# Power_Supply.net
KiCad netlist of a schematic drawn in Altium Designer
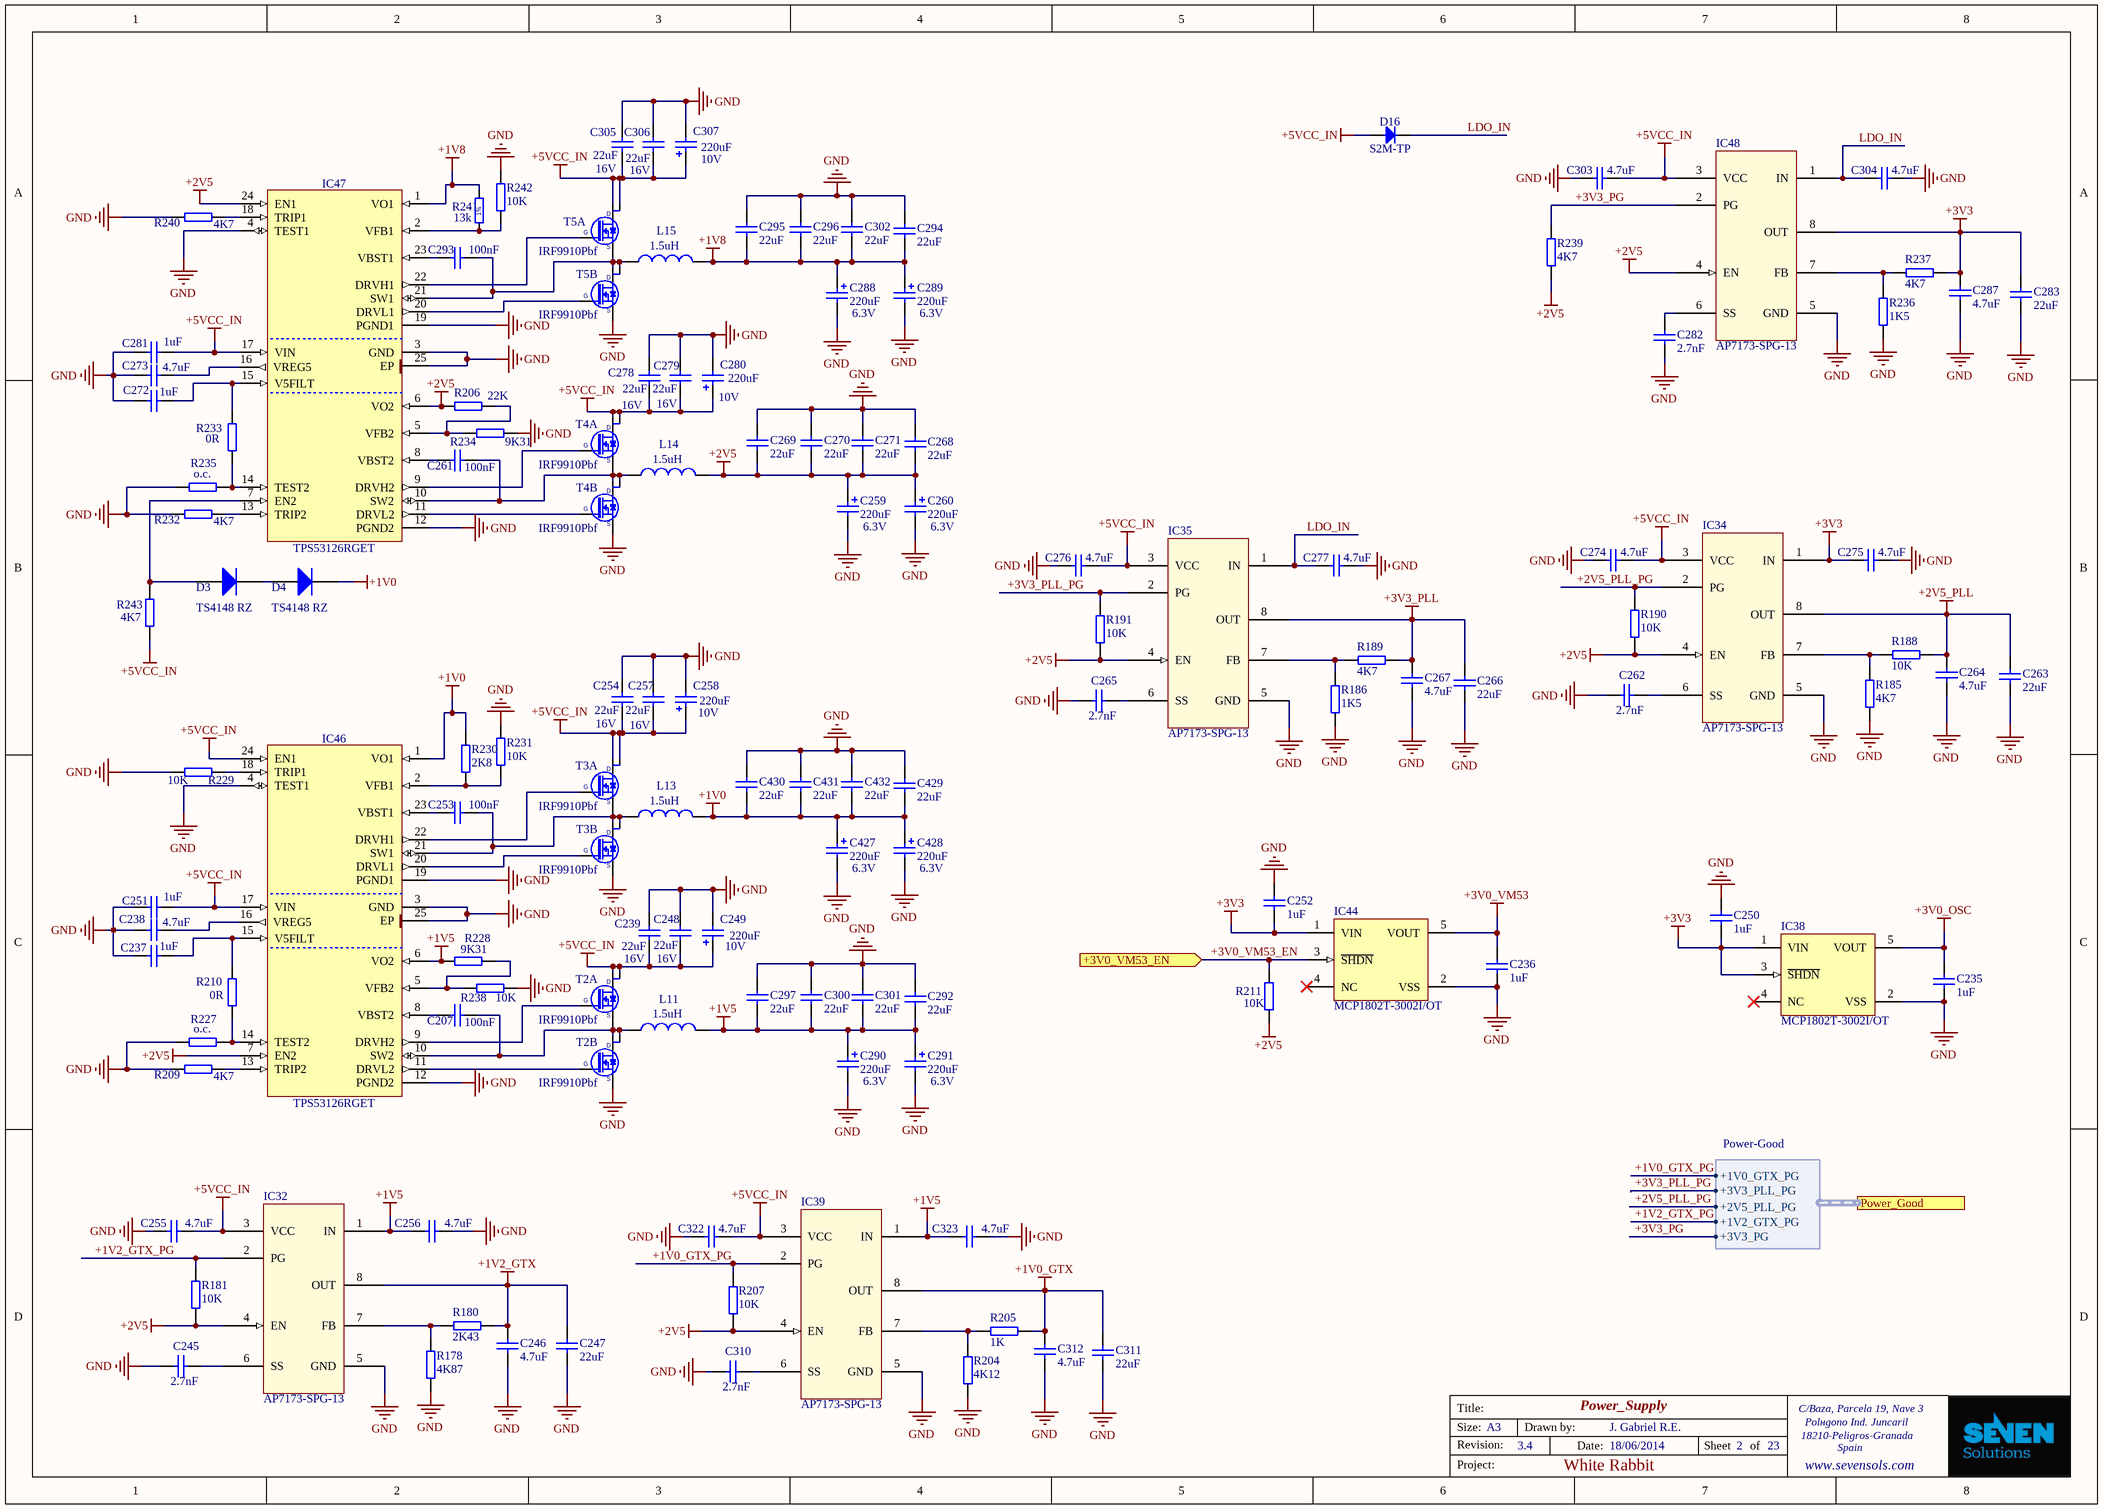
[diagram p0: Power_Supply.SchDoc]

(export (version "E")
  (design (tool "Eeschema 10.0.6"))
  (components
    (comp (ref "C207")
      (value "100nF")
      (footprint "CC1005-0402")
      (description "Capacitor")
      (fields
        (field (name "TOLERANCE") "±10%")
        (field (name "VOLTAGE") "16V")
        (field (name "PUBLISHER") "Altium Limited")
      )
      (libsource (lib "wr_switch") (part "Cap"))
    )
    (comp (ref "C235")
      (value "1uF")
      (footprint "CC1005-0402")
      (description "Capacitor")
      (fields
        (field (name "TOLERANCE") "±10%")
        (field (name "VOLTAGE") "16V")
        (field (name "PUBLISHER") "Altium Limited")
      )
      (libsource (lib "wr_switch") (part "Cap"))
    )
    (comp (ref "C236")
      (value "1uF")
      (footprint "CC1005-0402")
      (description "Capacitor")
      (fields
        (field (name "TOLERANCE") "±10%")
        (field (name "VOLTAGE") "16V")
        (field (name "PUBLISHER") "Altium Limited")
      )
      (libsource (lib "wr_switch") (part "Cap"))
    )
    (comp (ref "C237")
      (value "1uF")
      (footprint "CC1005-0402")
      (description "Capacitor")
      (fields
        (field (name "TOLERANCE") "±10%")
        (field (name "VOLTAGE") "16V")
        (field (name "PUBLISHER") "Altium Limited")
      )
      (libsource (lib "wr_switch") (part "Cap"))
    )
    (comp (ref "C238")
      (value "4.7uF")
      (footprint "CC1608-0603")
      (description "Capacitor")
      (fields
        (field (name "TOLERANCE") "±10%")
        (field (name "VOLTAGE") "10V")
        (field (name "PUBLISHER") "Altium Limited")
      )
      (libsource (lib "wr_switch") (part "Cap"))
    )
    (comp (ref "C239")
      (value "22uF")
      (footprint "CC2012-0805")
      (description "Capacitor")
      (fields
        (field (name "TOLERANCE") "±10%")
        (field (name "VOLTAGE") "16V")
        (field (name "Comment") "22uF 16V")
        (field (name "PUBLISHER") "Altium Limited")
      )
      (libsource (lib "wr_switch") (part "Cap"))
    )
    (comp (ref "C245")
      (value "2.7nF")
      (footprint "CC1005-0402")
      (description "Capacitor")
      (fields
        (field (name "TOLERANCE") "±10%")
        (field (name "VOLTAGE") "50V")
        (field (name "PUBLISHER") "Altium Limited")
      )
      (libsource (lib "wr_switch") (part "Cap"))
    )
    (comp (ref "C246")
      (value "4.7uF")
      (footprint "CC1608-0603")
      (description "Capacitor")
      (fields
        (field (name "TOLERANCE") "±10%")
        (field (name "VOLTAGE") "10V")
        (field (name "PUBLISHER") "Altium Limited")
      )
      (libsource (lib "wr_switch") (part "Cap"))
    )
    (comp (ref "C247")
      (value "22uF")
      (footprint "CC2012-0805")
      (description "Capacitor")
      (fields
        (field (name "TOLERANCE") "±20%")
        (field (name "VOLTAGE") "6.3V")
        (field (name "PUBLISHER") "Altium Limited")
      )
      (libsource (lib "wr_switch") (part "Cap"))
    )
    (comp (ref "C248")
      (value "22uF")
      (footprint "CC2012-0805")
      (description "Capacitor")
      (fields
        (field (name "TOLERANCE") "±10%")
        (field (name "VOLTAGE") "16V")
        (field (name "Comment") "22uF 16V")
        (field (name "PUBLISHER") "Altium Limited")
      )
      (libsource (lib "wr_switch") (part "Cap"))
    )
    (comp (ref "C249")
      (value "220uF")
      (footprint "D")
      (description "Polarized Capacitor Tantalum")
      (fields
        (field (name "TOLERANCE") "±20%")
        (field (name "VOLTAGE") "10V")
        (field (name "Comment") "220uF 10V")
        (field (name "PUBLISHER") "Altium Limited")
      )
      (libsource (lib "wr_switch") (part "Cap Pol1"))
    )
    (comp (ref "C250")
      (value "1uF")
      (footprint "CC1005-0402")
      (description "Capacitor")
      (fields
        (field (name "TOLERANCE") "±10%")
        (field (name "VOLTAGE") "16V")
        (field (name "PUBLISHER") "Altium Limited")
      )
      (libsource (lib "wr_switch") (part "Cap"))
    )
    (comp (ref "C251")
      (value "1uF")
      (footprint "CC1005-0402")
      (description "Capacitor")
      (fields
        (field (name "TOLERANCE") "±10%")
        (field (name "VOLTAGE") "16V")
        (field (name "PUBLISHER") "Altium Limited")
      )
      (libsource (lib "wr_switch") (part "Cap"))
    )
    (comp (ref "C252")
      (value "1uF")
      (footprint "CC1005-0402")
      (description "Capacitor")
      (fields
        (field (name "TOLERANCE") "±10%")
        (field (name "VOLTAGE") "16V")
        (field (name "PUBLISHER") "Altium Limited")
      )
      (libsource (lib "wr_switch") (part "Cap"))
    )
    (comp (ref "C253")
      (value "100nF")
      (footprint "CC1005-0402")
      (description "Capacitor")
      (fields
        (field (name "TOLERANCE") "±10%")
        (field (name "VOLTAGE") "16V")
        (field (name "PUBLISHER") "Altium Limited")
      )
      (libsource (lib "wr_switch") (part "Cap"))
    )
    (comp (ref "C254")
      (value "22uF")
      (footprint "CC2012-0805")
      (description "Capacitor")
      (fields
        (field (name "TOLERANCE") "±10%")
        (field (name "VOLTAGE") "16V")
        (field (name "Comment") "22uF 16V")
        (field (name "PUBLISHER") "Altium Limited")
      )
      (libsource (lib "wr_switch") (part "Cap"))
    )
    (comp (ref "C255")
      (value "4.7uF")
      (footprint "CC1608-0603")
      (description "Capacitor")
      (fields
        (field (name "TOLERANCE") "±10%")
        (field (name "VOLTAGE") "10V")
        (field (name "PUBLISHER") "Altium Limited")
      )
      (libsource (lib "wr_switch") (part "Cap"))
    )
    (comp (ref "C256")
      (value "4.7uF")
      (footprint "CC1608-0603")
      (description "Capacitor")
      (fields
        (field (name "TOLERANCE") "±10%")
        (field (name "VOLTAGE") "10V")
        (field (name "PUBLISHER") "Altium Limited")
      )
      (libsource (lib "wr_switch") (part "Cap"))
    )
    (comp (ref "C257")
      (value "22uF")
      (footprint "CC2012-0805")
      (description "Capacitor")
      (fields
        (field (name "TOLERANCE") "±10%")
        (field (name "VOLTAGE") "16V")
        (field (name "Comment") "22uF 16V")
        (field (name "PUBLISHER") "Altium Limited")
      )
      (libsource (lib "wr_switch") (part "Cap"))
    )
    (comp (ref "C258")
      (value "220uF")
      (footprint "D")
      (description "Polarized Capacitor Tantalum")
      (fields
        (field (name "TOLERANCE") "±20%")
        (field (name "VOLTAGE") "10V")
        (field (name "Comment") "220uF 10V")
        (field (name "PUBLISHER") "Altium Limited")
      )
      (libsource (lib "wr_switch") (part "Cap Pol1"))
    )
    (comp (ref "C259")
      (value "220uF")
      (footprint "D")
      (description "Polarized Capacitor Tantalum")
      (fields
        (field (name "TOLERANCE") "±20%")
        (field (name "VOLTAGE") "6.3V")
        (field (name "PUBLISHER") "Altium Limited")
      )
      (libsource (lib "wr_switch") (part "Cap Pol1"))
    )
    (comp (ref "C260")
      (value "220uF")
      (footprint "D")
      (description "Polarized Capacitor Tantalum")
      (fields
        (field (name "TOLERANCE") "±20%")
        (field (name "VOLTAGE") "6.3V")
        (field (name "PUBLISHER") "Altium Limited")
      )
      (libsource (lib "wr_switch") (part "Cap Pol1"))
    )
    (comp (ref "C261")
      (value "100nF")
      (footprint "CC1005-0402")
      (description "Capacitor")
      (fields
        (field (name "TOLERANCE") "±10%")
        (field (name "VOLTAGE") "16V")
        (field (name "PUBLISHER") "Altium Limited")
      )
      (libsource (lib "wr_switch") (part "Cap"))
    )
    (comp (ref "C262")
      (value "2.7nF")
      (footprint "CC1005-0402")
      (description "Capacitor")
      (fields
        (field (name "TOLERANCE") "±10%")
        (field (name "VOLTAGE") "50V")
        (field (name "PUBLISHER") "Altium Limited")
      )
      (libsource (lib "wr_switch") (part "Cap"))
    )
    (comp (ref "C263")
      (value "22uF")
      (footprint "CC2012-0805")
      (description "Capacitor")
      (fields
        (field (name "TOLERANCE") "±20%")
        (field (name "VOLTAGE") "6.3V")
        (field (name "PUBLISHER") "Altium Limited")
      )
      (libsource (lib "wr_switch") (part "Cap"))
    )
    (comp (ref "C264")
      (value "4.7uF")
      (footprint "CC1608-0603")
      (description "Capacitor")
      (fields
        (field (name "TOLERANCE") "±10%")
        (field (name "VOLTAGE") "10V")
        (field (name "PUBLISHER") "Altium Limited")
      )
      (libsource (lib "wr_switch") (part "Cap"))
    )
    (comp (ref "C265")
      (value "2.7nF")
      (footprint "CC1005-0402")
      (description "Capacitor")
      (fields
        (field (name "TOLERANCE") "±10%")
        (field (name "VOLTAGE") "50V")
        (field (name "PUBLISHER") "Altium Limited")
      )
      (libsource (lib "wr_switch") (part "Cap"))
    )
    (comp (ref "C266")
      (value "22uF")
      (footprint "CC2012-0805")
      (description "Capacitor")
      (fields
        (field (name "TOLERANCE") "±20%")
        (field (name "VOLTAGE") "6.3V")
        (field (name "PUBLISHER") "Altium Limited")
      )
      (libsource (lib "wr_switch") (part "Cap"))
    )
    (comp (ref "C267")
      (value "4.7uF")
      (footprint "CC1608-0603")
      (description "Capacitor")
      (fields
        (field (name "TOLERANCE") "±10%")
        (field (name "VOLTAGE") "10V")
        (field (name "PUBLISHER") "Altium Limited")
      )
      (libsource (lib "wr_switch") (part "Cap"))
    )
    (comp (ref "C268")
      (value "22uF")
      (footprint "CC2012-0805")
      (description "Capacitor")
      (fields
        (field (name "TOLERANCE") "±20%")
        (field (name "VOLTAGE") "6.3V")
        (field (name "PUBLISHER") "Altium Limited")
      )
      (libsource (lib "wr_switch") (part "Cap"))
    )
    (comp (ref "C269")
      (value "22uF")
      (footprint "CC2012-0805")
      (description "Capacitor")
      (fields
        (field (name "TOLERANCE") "±20%")
        (field (name "VOLTAGE") "6.3V")
        (field (name "PUBLISHER") "Altium Limited")
      )
      (libsource (lib "wr_switch") (part "Cap"))
    )
    (comp (ref "C270")
      (value "22uF")
      (footprint "CC2012-0805")
      (description "Capacitor")
      (fields
        (field (name "TOLERANCE") "±20%")
        (field (name "VOLTAGE") "6.3V")
        (field (name "PUBLISHER") "Altium Limited")
      )
      (libsource (lib "wr_switch") (part "Cap"))
    )
    (comp (ref "C271")
      (value "22uF")
      (footprint "CC2012-0805")
      (description "Capacitor")
      (fields
        (field (name "TOLERANCE") "±20%")
        (field (name "VOLTAGE") "6.3V")
        (field (name "PUBLISHER") "Altium Limited")
      )
      (libsource (lib "wr_switch") (part "Cap"))
    )
    (comp (ref "C272")
      (value "1uF")
      (footprint "CC1005-0402")
      (description "Capacitor")
      (fields
        (field (name "TOLERANCE") "±10%")
        (field (name "VOLTAGE") "16V")
        (field (name "PUBLISHER") "Altium Limited")
      )
      (libsource (lib "wr_switch") (part "Cap"))
    )
    (comp (ref "C273")
      (value "4.7uF")
      (footprint "CC1608-0603")
      (description "Capacitor")
      (fields
        (field (name "TOLERANCE") "±10%")
        (field (name "VOLTAGE") "10V")
        (field (name "PUBLISHER") "Altium Limited")
      )
      (libsource (lib "wr_switch") (part "Cap"))
    )
    (comp (ref "C274")
      (value "4.7uF")
      (footprint "CC1608-0603")
      (description "Capacitor")
      (fields
        (field (name "TOLERANCE") "±10%")
        (field (name "VOLTAGE") "10V")
        (field (name "PUBLISHER") "Altium Limited")
      )
      (libsource (lib "wr_switch") (part "Cap"))
    )
    (comp (ref "C275")
      (value "4.7uF")
      (footprint "CC1608-0603")
      (description "Capacitor")
      (fields
        (field (name "TOLERANCE") "±10%")
        (field (name "VOLTAGE") "10V")
        (field (name "PUBLISHER") "Altium Limited")
      )
      (libsource (lib "wr_switch") (part "Cap"))
    )
    (comp (ref "C276")
      (value "4.7uF")
      (footprint "CC1608-0603")
      (description "Capacitor")
      (fields
        (field (name "TOLERANCE") "±10%")
        (field (name "VOLTAGE") "10V")
        (field (name "PUBLISHER") "Altium Limited")
      )
      (libsource (lib "wr_switch") (part "Cap"))
    )
    (comp (ref "C277")
      (value "4.7uF")
      (footprint "CC1608-0603")
      (description "Capacitor")
      (fields
        (field (name "TOLERANCE") "±10%")
        (field (name "VOLTAGE") "10V")
        (field (name "PUBLISHER") "Altium Limited")
      )
      (libsource (lib "wr_switch") (part "Cap"))
    )
    (comp (ref "C278")
      (value "22uF")
      (footprint "CC2012-0805")
      (description "Capacitor")
      (fields
        (field (name "TOLERANCE") "±10%")
        (field (name "VOLTAGE") "16V")
        (field (name "Comment") "22uF 16V")
        (field (name "PUBLISHER") "Altium Limited")
      )
      (libsource (lib "wr_switch") (part "Cap"))
    )
    (comp (ref "C279")
      (value "22uF")
      (footprint "CC2012-0805")
      (description "Capacitor")
      (fields
        (field (name "TOLERANCE") "±10%")
        (field (name "VOLTAGE") "16V")
        (field (name "Comment") "22uF 16V")
        (field (name "PUBLISHER") "Altium Limited")
      )
      (libsource (lib "wr_switch") (part "Cap"))
    )
    (comp (ref "C280")
      (value "220uF")
      (footprint "D")
      (description "Polarized Capacitor Tantalum")
      (fields
        (field (name "TOLERANCE") "±20%")
        (field (name "VOLTAGE") "10V")
        (field (name "Comment") "220uF 10V")
        (field (name "PUBLISHER") "Altium Limited")
      )
      (libsource (lib "wr_switch") (part "Cap Pol1"))
    )
    (comp (ref "C281")
      (value "1uF")
      (footprint "CC1005-0402")
      (description "Capacitor")
      (fields
        (field (name "TOLERANCE") "±10%")
        (field (name "VOLTAGE") "16V")
        (field (name "PUBLISHER") "Altium Limited")
      )
      (libsource (lib "wr_switch") (part "Cap"))
    )
    (comp (ref "C282")
      (value "2.7nF")
      (footprint "CC1005-0402")
      (description "Capacitor")
      (fields
        (field (name "TOLERANCE") "±10%")
        (field (name "VOLTAGE") "50V")
        (field (name "PUBLISHER") "Altium Limited")
      )
      (libsource (lib "wr_switch") (part "Cap"))
    )
    (comp (ref "C283")
      (value "22uF")
      (footprint "CC2012-0805")
      (description "Capacitor")
      (fields
        (field (name "TOLERANCE") "±20%")
        (field (name "VOLTAGE") "6.3V")
        (field (name "PUBLISHER") "Altium Limited")
      )
      (libsource (lib "wr_switch") (part "Cap"))
    )
    (comp (ref "C287")
      (value "4.7uF")
      (footprint "CC1608-0603")
      (description "Capacitor")
      (fields
        (field (name "TOLERANCE") "±10%")
        (field (name "VOLTAGE") "10V")
        (field (name "PUBLISHER") "Altium Limited")
      )
      (libsource (lib "wr_switch") (part "Cap"))
    )
    (comp (ref "C288")
      (value "220uF")
      (footprint "D")
      (description "Polarized Capacitor Tantalum")
      (fields
        (field (name "TOLERANCE") "±20%")
        (field (name "VOLTAGE") "6.3V")
        (field (name "PUBLISHER") "Altium Limited")
      )
      (libsource (lib "wr_switch") (part "Cap Pol1"))
    )
    (comp (ref "C289")
      (value "220uF")
      (footprint "D")
      (description "Polarized Capacitor Tantalum")
      (fields
        (field (name "TOLERANCE") "±20%")
        (field (name "VOLTAGE") "6.3V")
        (field (name "PUBLISHER") "Altium Limited")
      )
      (libsource (lib "wr_switch") (part "Cap Pol1"))
    )
    (comp (ref "C290")
      (value "220uF")
      (footprint "D")
      (description "Polarized Capacitor Tantalum")
      (fields
        (field (name "TOLERANCE") "±20%")
        (field (name "VOLTAGE") "6.3V")
        (field (name "PUBLISHER") "Altium Limited")
      )
      (libsource (lib "wr_switch") (part "Cap Pol1"))
    )
    (comp (ref "C291")
      (value "220uF")
      (footprint "D")
      (description "Polarized Capacitor Tantalum")
      (fields
        (field (name "TOLERANCE") "±20%")
        (field (name "VOLTAGE") "6.3V")
        (field (name "PUBLISHER") "Altium Limited")
      )
      (libsource (lib "wr_switch") (part "Cap Pol1"))
    )
    (comp (ref "C292")
      (value "22uF")
      (footprint "CC2012-0805")
      (description "Capacitor")
      (fields
        (field (name "TOLERANCE") "±20%")
        (field (name "VOLTAGE") "6.3V")
        (field (name "PUBLISHER") "Altium Limited")
      )
      (libsource (lib "wr_switch") (part "Cap"))
    )
    (comp (ref "C293")
      (value "100nF")
      (footprint "CC1005-0402")
      (description "Capacitor")
      (fields
        (field (name "TOLERANCE") "±10%")
        (field (name "VOLTAGE") "16V")
        (field (name "PUBLISHER") "Altium Limited")
      )
      (libsource (lib "wr_switch") (part "Cap"))
    )
    (comp (ref "C294")
      (value "22uF")
      (footprint "CC2012-0805")
      (description "Capacitor")
      (fields
        (field (name "TOLERANCE") "±20%")
        (field (name "VOLTAGE") "6.3V")
        (field (name "PUBLISHER") "Altium Limited")
      )
      (libsource (lib "wr_switch") (part "Cap"))
    )
    (comp (ref "C295")
      (value "22uF")
      (footprint "CC2012-0805")
      (description "Capacitor")
      (fields
        (field (name "TOLERANCE") "±20%")
        (field (name "VOLTAGE") "6.3V")
        (field (name "PUBLISHER") "Altium Limited")
      )
      (libsource (lib "wr_switch") (part "Cap"))
    )
    (comp (ref "C296")
      (value "22uF")
      (footprint "CC2012-0805")
      (description "Capacitor")
      (fields
        (field (name "TOLERANCE") "±20%")
        (field (name "VOLTAGE") "6.3V")
        (field (name "PUBLISHER") "Altium Limited")
      )
      (libsource (lib "wr_switch") (part "Cap"))
    )
    (comp (ref "C297")
      (value "22uF")
      (footprint "CC2012-0805")
      (description "Capacitor")
      (fields
        (field (name "TOLERANCE") "±20%")
        (field (name "VOLTAGE") "6.3V")
        (field (name "PUBLISHER") "Altium Limited")
      )
      (libsource (lib "wr_switch") (part "Cap"))
    )
    (comp (ref "C300")
      (value "22uF")
      (footprint "CC2012-0805")
      (description "Capacitor")
      (fields
        (field (name "TOLERANCE") "±20%")
        (field (name "VOLTAGE") "6.3V")
        (field (name "PUBLISHER") "Altium Limited")
      )
      (libsource (lib "wr_switch") (part "Cap"))
    )
    (comp (ref "C301")
      (value "22uF")
      (footprint "CC2012-0805")
      (description "Capacitor")
      (fields
        (field (name "TOLERANCE") "±20%")
        (field (name "VOLTAGE") "6.3V")
        (field (name "PUBLISHER") "Altium Limited")
      )
      (libsource (lib "wr_switch") (part "Cap"))
    )
    (comp (ref "C302")
      (value "22uF")
      (footprint "CC2012-0805")
      (description "Capacitor")
      (fields
        (field (name "TOLERANCE") "±20%")
        (field (name "VOLTAGE") "6.3V")
        (field (name "PUBLISHER") "Altium Limited")
      )
      (libsource (lib "wr_switch") (part "Cap"))
    )
    (comp (ref "C303")
      (value "4.7uF")
      (footprint "CC1608-0603")
      (description "Capacitor")
      (fields
        (field (name "TOLERANCE") "±10%")
        (field (name "VOLTAGE") "10V")
        (field (name "PUBLISHER") "Altium Limited")
      )
      (libsource (lib "wr_switch") (part "Cap"))
    )
    (comp (ref "C304")
      (value "4.7uF")
      (footprint "CC1608-0603")
      (description "Capacitor")
      (fields
        (field (name "TOLERANCE") "±10%")
        (field (name "VOLTAGE") "10V")
        (field (name "PUBLISHER") "Altium Limited")
      )
      (libsource (lib "wr_switch") (part "Cap"))
    )
    (comp (ref "C305")
      (value "22uF")
      (footprint "CC2012-0805")
      (description "Capacitor")
      (fields
        (field (name "TOLERANCE") "±10%")
        (field (name "VOLTAGE") "16V")
        (field (name "Comment") "22uF 16V")
        (field (name "PUBLISHER") "Altium Limited")
      )
      (libsource (lib "wr_switch") (part "Cap"))
    )
    (comp (ref "C306")
      (value "22uF")
      (footprint "CC2012-0805")
      (description "Capacitor")
      (fields
        (field (name "TOLERANCE") "±10%")
        (field (name "VOLTAGE") "16V")
        (field (name "Comment") "22uF 16V")
        (field (name "PUBLISHER") "Altium Limited")
      )
      (libsource (lib "wr_switch") (part "Cap"))
    )
    (comp (ref "C307")
      (value "220uF")
      (footprint "D")
      (description "Polarized Capacitor Tantalum")
      (fields
        (field (name "TOLERANCE") "±20%")
        (field (name "VOLTAGE") "10V")
        (field (name "Comment") "220uF 10V")
        (field (name "PUBLISHER") "Altium Limited")
      )
      (libsource (lib "wr_switch") (part "Cap Pol1"))
    )
    (comp (ref "C310")
      (value "2.7nF")
      (footprint "CC1005-0402")
      (description "Capacitor")
      (fields
        (field (name "TOLERANCE") "±10%")
        (field (name "VOLTAGE") "50V")
        (field (name "PUBLISHER") "Altium Limited")
      )
      (libsource (lib "wr_switch") (part "Cap"))
    )
    (comp (ref "C311")
      (value "22uF")
      (footprint "CC2012-0805")
      (description "Capacitor")
      (fields
        (field (name "TOLERANCE") "±20%")
        (field (name "VOLTAGE") "6.3V")
        (field (name "PUBLISHER") "Altium Limited")
      )
      (libsource (lib "wr_switch") (part "Cap"))
    )
    (comp (ref "C312")
      (value "4.7uF")
      (footprint "CC1608-0603")
      (description "Capacitor")
      (fields
        (field (name "TOLERANCE") "±10%")
        (field (name "VOLTAGE") "10V")
        (field (name "PUBLISHER") "Altium Limited")
      )
      (libsource (lib "wr_switch") (part "Cap"))
    )
    (comp (ref "C322")
      (value "4.7uF")
      (footprint "CC1608-0603")
      (description "Capacitor")
      (fields
        (field (name "TOLERANCE") "±10%")
        (field (name "VOLTAGE") "10V")
        (field (name "PUBLISHER") "Altium Limited")
      )
      (libsource (lib "wr_switch") (part "Cap"))
    )
    (comp (ref "C323")
      (value "4.7uF")
      (footprint "CC1608-0603")
      (description "Capacitor")
      (fields
        (field (name "TOLERANCE") "±10%")
        (field (name "VOLTAGE") "10V")
        (field (name "PUBLISHER") "Altium Limited")
      )
      (libsource (lib "wr_switch") (part "Cap"))
    )
    (comp (ref "C427")
      (value "220uF")
      (footprint "D")
      (description "Polarized Capacitor Tantalum")
      (fields
        (field (name "TOLERANCE") "±20%")
        (field (name "VOLTAGE") "6.3V")
        (field (name "PUBLISHER") "Altium Limited")
      )
      (libsource (lib "wr_switch") (part "Cap Pol1"))
    )
    (comp (ref "C428")
      (value "220uF")
      (footprint "D")
      (description "Polarized Capacitor Tantalum")
      (fields
        (field (name "TOLERANCE") "±20%")
        (field (name "VOLTAGE") "6.3V")
        (field (name "PUBLISHER") "Altium Limited")
      )
      (libsource (lib "wr_switch") (part "Cap Pol1"))
    )
    (comp (ref "C429")
      (value "22uF")
      (footprint "CC2012-0805")
      (description "Capacitor")
      (fields
        (field (name "TOLERANCE") "±20%")
        (field (name "VOLTAGE") "6.3V")
        (field (name "PUBLISHER") "Altium Limited")
      )
      (libsource (lib "wr_switch") (part "Cap"))
    )
    (comp (ref "C430")
      (value "22uF")
      (footprint "CC2012-0805")
      (description "Capacitor")
      (fields
        (field (name "TOLERANCE") "±20%")
        (field (name "VOLTAGE") "6.3V")
        (field (name "PUBLISHER") "Altium Limited")
      )
      (libsource (lib "wr_switch") (part "Cap"))
    )
    (comp (ref "C431")
      (value "22uF")
      (footprint "CC2012-0805")
      (description "Capacitor")
      (fields
        (field (name "TOLERANCE") "±20%")
        (field (name "VOLTAGE") "6.3V")
        (field (name "PUBLISHER") "Altium Limited")
      )
      (libsource (lib "wr_switch") (part "Cap"))
    )
    (comp (ref "C432")
      (value "22uF")
      (footprint "CC2012-0805")
      (description "Capacitor")
      (fields
        (field (name "TOLERANCE") "±20%")
        (field (name "VOLTAGE") "6.3V")
        (field (name "PUBLISHER") "Altium Limited")
      )
      (libsource (lib "wr_switch") (part "Cap"))
    )
    (comp (ref "D3")
      (value "TS4148 RZ")
      (footprint "CD1608-0603")
      (description "Default Diode")
      (fields (field (name "PUBLISHER") "Altium Limited"))
      (libsource (lib "Miscellaneous Devices") (part "Diode"))
    )
    (comp (ref "D4")
      (value "TS4148 RZ")
      (footprint "CD1608-0603")
      (description "Default Diode")
      (fields (field (name "PUBLISHER") "Altium Limited"))
      (libsource (lib "Miscellaneous Devices") (part "Diode"))
    )
    (comp (ref "D16")
      (value "S2M-TP")
      (footprint "DO-214AA/SMB-MCC")
      (description "2 A Silicon Rectifier 50 to 1000 Volts")
      (fields (field (name "AUTHOR") "CERN DEM JLC"))
      (libsource (lib "wr_switch") (part "S2M-TP"))
    )
    (comp (ref "IC32")
      (value "AP7173-SPG-13")
      (footprint "7S_WR:SOIC127P600-8AL-ThermalPad")
      (description "1.5A Low Dropout Linera Regulator")
      (libsource (lib "wr_switch") (part "AP7173"))
    )
    (comp (ref "IC34")
      (value "AP7173-SPG-13")
      (footprint "7S_WR:SOIC127P600-8AL-ThermalPad")
      (description "1.5A Low Dropout Linera Regulator")
      (libsource (lib "wr_switch") (part "AP7173"))
    )
    (comp (ref "IC35")
      (value "AP7173-SPG-13")
      (footprint "7S_WR:SOIC127P600-8AL-ThermalPad")
      (description "1.5A Low Dropout Linera Regulator")
      (libsource (lib "wr_switch") (part "AP7173"))
    )
    (comp (ref "IC38")
      (value "MCP1802T-3002I/OT")
      (footprint "SOT-23-OT5_N")
      (description "300 mA, High PSRR, Low Quiescent Current LDO, 5-Pin SOT-23, Industrial Temperature, Tape and Reel")
      (fields (field (name "PUBLISHER") "Altium Limited"))
      (libsource (lib "Microchip Power Mgt Line Regulator") (part "MCP1802T-3002I/OT"))
    )
    (comp (ref "IC39")
      (value "AP7173-SPG-13")
      (footprint "7S_WR:SOIC127P600-8AL-ThermalPad")
      (description "1.5A Low Dropout Linera Regulator")
      (libsource (lib "wr_switch") (part "AP7173"))
    )
    (comp (ref "IC44")
      (value "MCP1802T-3002I/OT")
      (footprint "SOT-23-OT5_N")
      (description "300 mA, High PSRR, Low Quiescent Current LDO, 5-Pin SOT-23, Industrial Temperature, Tape and Reel")
      (fields (field (name "PUBLISHER") "Altium Limited"))
      (libsource (lib "Microchip Power Mgt Line Regulator") (part "MCP1802T-3002I/OT"))
    )
    (comp (ref "IC46")
      (value "TPS53126RGET")
      (footprint "QFN50P400X400X100-25N-S255")
      (description "Dual Synchronous Step-Down Controller For Low Voltage Power Rails")
      (fields (field (name "MANUFACTURER") "TEXAS INSTRUMENTS") (field (name "AUTHOR") "CERN DEM JLC"))
      (libsource (lib "wr_switch") (part "TPS53126RGET"))
    )
    (comp (ref "IC47")
      (value "TPS53126RGET")
      (footprint "QFN50P400X400X100-25N-S255")
      (description "Dual Synchronous Step-Down Controller For Low Voltage Power Rails")
      (fields (field (name "MANUFACTURER") "TEXAS INSTRUMENTS") (field (name "AUTHOR") "CERN DEM JLC"))
      (libsource (lib "wr_switch") (part "TPS53126RGET"))
    )
    (comp (ref "IC48")
      (value "AP7173-SPG-13")
      (footprint "7S_WR:SOIC127P600-8AL-ThermalPad")
      (description "1.5A Low Dropout Linera Regulator")
      (libsource (lib "wr_switch") (part "AP7173"))
    )
    (comp (ref "L11")
      (value "1.5uH")
      (footprint "IHLP2525")
      (description "Low Profile, High Current Inductor")
      (fields
        (field (name "MANUFACTURER") "Vishay/Dale")
        (field (name "Comment") "IHLP2525CZER1R5M01")
        (field (name "PUBLISHER") "Altium Limited")
      )
      (libsource (lib "Miscellaneous Devices") (part "Inductor"))
    )
    (comp (ref "L13")
      (value "1.5uH")
      (footprint "IHLP2525")
      (description "Low Profile, High Current Inductor")
      (fields
        (field (name "MANUFACTURER") "Vishay/Dale")
        (field (name "Comment") "IHLP2525CZER1R5M01")
        (field (name "PUBLISHER") "Altium Limited")
      )
      (libsource (lib "Miscellaneous Devices") (part "Inductor"))
    )
    (comp (ref "L14")
      (value "1.5uH")
      (footprint "IHLP2525")
      (description "Low Profile, High Current Inductor")
      (fields
        (field (name "MANUFACTURER") "Vishay/Dale")
        (field (name "Comment") "IHLP2525CZER1R5M01")
        (field (name "PUBLISHER") "Altium Limited")
      )
      (libsource (lib "Miscellaneous Devices") (part "Inductor"))
    )
    (comp (ref "L15")
      (value "1.5uH")
      (footprint "IHLP2525")
      (description "Low Profile, High Current Inductor")
      (fields
        (field (name "MANUFACTURER") "Vishay/Dale")
        (field (name "Comment") "IHLP2525CZER1R5M01")
        (field (name "PUBLISHER") "Altium Limited")
      )
      (libsource (lib "Miscellaneous Devices") (part "Inductor"))
    )
    (comp (ref "R178")
      (value "4K87")
      (footprint "0402")
      (description "SMD Resistor")
      (fields (field (name "TOLERANCE") "±1%"))
      (libsource (lib "wr_switch") (part "RES_SMD"))
    )
    (comp (ref "R180")
      (value "2K43")
      (footprint "0402")
      (description "SMD Resistor")
      (fields (field (name "TOLERANCE") "±1%"))
      (libsource (lib "wr_switch") (part "RES_SMD"))
    )
    (comp (ref "R181")
      (value "10K")
      (footprint "0402")
      (description "SMD Resistor")
      (fields (field (name "TOLERANCE") "±1%") (field (name "Comment") "10k"))
      (libsource (lib "wr_switch") (part "RES_SMD"))
    )
    (comp (ref "R185")
      (value "4K7")
      (footprint "0402")
      (description "SMD Resistor")
      (fields (field (name "TOLERANCE") "±1%"))
      (libsource (lib "wr_switch") (part "RES_SMD"))
    )
    (comp (ref "R186")
      (value "1K5")
      (footprint "0402")
      (description "SMD Resistor")
      (fields (field (name "TOLERANCE") "±1%"))
      (libsource (lib "wr_switch") (part "RES_SMD"))
    )
    (comp (ref "R188")
      (value "10K")
      (footprint "0402")
      (description "SMD Resistor")
      (fields (field (name "TOLERANCE") "±1%"))
      (libsource (lib "wr_switch") (part "RES_SMD"))
    )
    (comp (ref "R189")
      (value "4K7")
      (footprint "0402")
      (description "SMD Resistor")
      (fields (field (name "TOLERANCE") "±1%"))
      (libsource (lib "wr_switch") (part "RES_SMD"))
    )
    (comp (ref "R190")
      (value "10K")
      (footprint "0402")
      (description "SMD Resistor")
      (fields (field (name "TOLERANCE") "±1%") (field (name "Comment") "10k"))
      (libsource (lib "wr_switch") (part "RES_SMD"))
    )
    (comp (ref "R191")
      (value "10K")
      (footprint "0402")
      (description "SMD Resistor")
      (fields (field (name "TOLERANCE") "±1%") (field (name "Comment") "10k"))
      (libsource (lib "wr_switch") (part "RES_SMD"))
    )
    (comp (ref "R204")
      (value "4K12")
      (footprint "0402")
      (description "SMD Resistor")
      (fields (field (name "TOLERANCE") "±1%"))
      (libsource (lib "wr_switch") (part "RES_SMD"))
    )
    (comp (ref "R205")
      (value "1K")
      (footprint "0402")
      (description "SMD Resistor")
      (fields (field (name "TOLERANCE") "±1%"))
      (libsource (lib "wr_switch") (part "RES_SMD"))
    )
    (comp (ref "R206")
      (value "22K")
      (footprint "0402")
      (description "SMD Resistor")
      (fields (field (name "TOLERANCE") "±1%"))
      (libsource (lib "wr_switch") (part "RES_SMD"))
    )
    (comp (ref "R207")
      (value "10K")
      (footprint "0402")
      (description "SMD Resistor")
      (fields (field (name "TOLERANCE") "±1%"))
      (libsource (lib "wr_switch") (part "RES_SMD"))
    )
    (comp (ref "R209")
      (value "4K7")
      (footprint "0402")
      (description "SMD Resistor")
      (fields (field (name "TOLERANCE") "±1%"))
      (libsource (lib "wr_switch") (part "RES_SMD"))
    )
    (comp (ref "R210")
      (value "0R")
      (footprint "0402")
      (description "SMD Resistor")
      (fields (field (name "TOLERANCE") "Jumper"))
      (libsource (lib "wr_switch") (part "RES_SMD"))
    )
    (comp (ref "R211")
      (value "10K")
      (footprint "0402")
      (description "SMD Resistor")
      (fields (field (name "TOLERANCE") "±1%") (field (name "Comment") "10k"))
      (libsource (lib "wr_switch") (part "RES_SMD"))
    )
    (comp (ref "R227")
      (value "o.c.")
      (footprint "0402")
      (description "SMD Resistor")
      (libsource (lib "wr_switch") (part "RES_SMD"))
    )
    (comp (ref "R228")
      (value "9K31")
      (footprint "0402")
      (description "SMD Resistor")
      (fields (field (name "TOLERANCE") "±1%"))
      (libsource (lib "wr_switch") (part "RES_SMD"))
    )
    (comp (ref "R229")
      (value "10K")
      (footprint "0402")
      (description "SMD Resistor")
      (fields (field (name "TOLERANCE") "±1%"))
      (libsource (lib "wr_switch") (part "RES_SMD"))
    )
    (comp (ref "R230")
      (value "2K8")
      (footprint "0402")
      (description "SMD Resistor")
      (fields (field (name "TOLERANCE") "±1%"))
      (libsource (lib "wr_switch") (part "RES_SMD"))
    )
    (comp (ref "R231")
      (value "10K")
      (footprint "0402")
      (description "SMD Resistor")
      (fields (field (name "TOLERANCE") "±1%"))
      (libsource (lib "wr_switch") (part "RES_SMD"))
    )
    (comp (ref "R232")
      (value "4K7")
      (footprint "0402")
      (description "SMD Resistor")
      (fields (field (name "TOLERANCE") "±1%"))
      (libsource (lib "wr_switch") (part "RES_SMD"))
    )
    (comp (ref "R233")
      (value "0R")
      (footprint "0402")
      (description "SMD Resistor")
      (fields (field (name "TOLERANCE") "Jumper"))
      (libsource (lib "wr_switch") (part "RES_SMD"))
    )
    (comp (ref "R234")
      (value "9K31")
      (footprint "0402")
      (description "SMD Resistor")
      (fields (field (name "TOLERANCE") "±1%"))
      (libsource (lib "wr_switch") (part "RES_SMD"))
    )
    (comp (ref "R235")
      (value "o.c.")
      (footprint "0402")
      (description "SMD Resistor")
      (libsource (lib "wr_switch") (part "RES_SMD"))
    )
    (comp (ref "R236")
      (value "1K5")
      (footprint "0402")
      (description "SMD Resistor")
      (fields (field (name "TOLERANCE") "±1%"))
      (libsource (lib "wr_switch") (part "RES_SMD"))
    )
    (comp (ref "R237")
      (value "4K7")
      (footprint "0402")
      (description "SMD Resistor")
      (fields (field (name "TOLERANCE") "±1%"))
      (libsource (lib "wr_switch") (part "RES_SMD"))
    )
    (comp (ref "R238")
      (value "10K")
      (footprint "0402")
      (description "SMD Resistor")
      (fields (field (name "TOLERANCE") "±1%"))
      (libsource (lib "wr_switch") (part "RES_SMD"))
    )
    (comp (ref "R239")
      (value "4K7")
      (footprint "0402")
      (description "SMD Resistor")
      (fields (field (name "TOLERANCE") "±1%"))
      (libsource (lib "wr_switch") (part "RES_SMD"))
    )
    (comp (ref "R240")
      (value "4K7")
      (footprint "0402")
      (description "SMD Resistor")
      (fields (field (name "TOLERANCE") "±1%"))
      (libsource (lib "wr_switch") (part "RES_SMD"))
    )
    (comp (ref "R241")
      (value "13k")
      (footprint "RESC1005X40N")
      (description "Resistor - 1%")
      (fields
        (field (name "PART NUMBER") "R0402_13K_1%_0.0625W_100PPM")
        (field (name "POWER") "0.0625W")
        (field (name "AUTHOR") "CERN DEM JLC")
      )
      (libsource (lib "Resistors") (part "Resistor - 1%"))
    )
    (comp (ref "R242")
      (value "10K")
      (footprint "0402")
      (description "SMD Resistor")
      (fields (field (name "TOLERANCE") "±1%"))
      (libsource (lib "wr_switch") (part "RES_SMD"))
    )
    (comp (ref "R243")
      (value "4K7")
      (footprint "0402")
      (description "SMD Resistor")
      (fields (field (name "TOLERANCE") "±1%"))
      (libsource (lib "wr_switch") (part "RES_SMD"))
    )
    (comp (ref "T2")
      (value "IRF9910Pbf")
      (footprint "SOIC127P600X175-8N")
      (description "Dual SO-8 MOSFET For POL Cconverter")
      (fields (field (name "MANUFACTURER") "INTERNATIONAL RECTIFIER") (field (name "AUTHOR") "CERN DEM JLC"))
      (libsource (lib "ICs And Semiconductors") (part "IRF9910"))
    )
    (comp (ref "T3")
      (value "IRF9910Pbf")
      (footprint "SOIC127P600X175-8N")
      (description "Dual SO-8 MOSFET For POL Cconverter")
      (fields (field (name "MANUFACTURER") "INTERNATIONAL RECTIFIER") (field (name "AUTHOR") "CERN DEM JLC"))
      (libsource (lib "ICs And Semiconductors") (part "IRF9910"))
    )
    (comp (ref "T4")
      (value "IRF9910Pbf")
      (footprint "SOIC127P600X175-8N")
      (description "Dual SO-8 MOSFET For POL Cconverter")
      (fields (field (name "MANUFACTURER") "INTERNATIONAL RECTIFIER") (field (name "AUTHOR") "CERN DEM JLC"))
      (libsource (lib "ICs And Semiconductors") (part "IRF9910"))
    )
    (comp (ref "T5")
      (value "IRF9910Pbf")
      (footprint "SOIC127P600X175-8N")
      (description "Dual SO-8 MOSFET For POL Cconverter")
      (fields (field (name "MANUFACTURER") "INTERNATIONAL RECTIFIER") (field (name "AUTHOR") "CERN DEM JLC"))
      (libsource (lib "ICs And Semiconductors") (part "IRF9910"))
    )
  )
  (nets
    (net (code "2") (name "+1V0") (class "Default")
      (node (ref "C427") (pin "1") (pinfunction "1_1") (pintype "passive"))
      (node (ref "C428") (pin "1") (pinfunction "1_1") (pintype "passive"))
      (node (ref "C429") (pin "1") (pinfunction "1_1") (pintype "passive"))
      (node (ref "C430") (pin "2") (pinfunction "2_2") (pintype "passive"))
      (node (ref "C431") (pin "1") (pinfunction "1_1") (pintype "passive"))
      (node (ref "C432") (pin "1") (pinfunction "1_1") (pintype "passive"))
      (node (ref "D4") (pin "2") (pinfunction "K_2") (pintype "passive"))
      (node (ref "IC46") (pin "1") (pinfunction "VO1_1") (pintype "input"))
      (node (ref "L13") (pin "2") (pinfunction "2_2") (pintype "passive"))
      (node (ref "R230") (pin "2") (pinfunction "2_2") (pintype "passive"))
    )
    (net (code "3") (name "+1V0_GTX") (class "Default")
      (node (ref "C311") (pin "2") (pinfunction "2_2") (pintype "passive"))
      (node (ref "C312") (pin "2") (pinfunction "2_2") (pintype "passive"))
      (node (ref "IC39") (pin "8") (pinfunction "OUT_8") (pintype "power_in"))
      (node (ref "R205") (pin "2") (pinfunction "2_2") (pintype "passive"))
    )
    (net (code "4") (name "+1V2_GTX") (class "Default")
      (node (ref "C246") (pin "2") (pinfunction "2_2") (pintype "passive"))
      (node (ref "C247") (pin "2") (pinfunction "2_2") (pintype "passive"))
      (node (ref "IC32") (pin "8") (pinfunction "OUT_8") (pintype "power_in"))
      (node (ref "R180") (pin "2") (pinfunction "2_2") (pintype "passive"))
    )
    (net (code "5") (name "+1V5") (class "Default")
      (node (ref "C256") (pin "1") (pinfunction "1_1") (pintype "passive"))
      (node (ref "C290") (pin "1") (pinfunction "1_1") (pintype "passive"))
      (node (ref "C291") (pin "1") (pinfunction "1_1") (pintype "passive"))
      (node (ref "C292") (pin "1") (pinfunction "1_1") (pintype "passive"))
      (node (ref "C297") (pin "2") (pinfunction "2_2") (pintype "passive"))
      (node (ref "C300") (pin "1") (pinfunction "1_1") (pintype "passive"))
      (node (ref "C301") (pin "1") (pinfunction "1_1") (pintype "passive"))
      (node (ref "C323") (pin "1") (pinfunction "1_1") (pintype "passive"))
      (node (ref "IC32") (pin "1") (pinfunction "IN_1") (pintype "power_in"))
      (node (ref "IC39") (pin "1") (pinfunction "IN_1") (pintype "power_in"))
      (node (ref "IC46") (pin "6") (pinfunction "VO2_6") (pintype "input"))
      (node (ref "L11") (pin "2") (pinfunction "2_2") (pintype "passive"))
      (node (ref "R228") (pin "1") (pinfunction "1_1") (pintype "passive"))
    )
    (net (code "6") (name "+1V8") (class "Default")
      (node (ref "C288") (pin "1") (pinfunction "1_1") (pintype "passive"))
      (node (ref "C289") (pin "1") (pinfunction "1_1") (pintype "passive"))
      (node (ref "C294") (pin "1") (pinfunction "1_1") (pintype "passive"))
      (node (ref "C295") (pin "2") (pinfunction "2_2") (pintype "passive"))
      (node (ref "C296") (pin "1") (pinfunction "1_1") (pintype "passive"))
      (node (ref "C302") (pin "1") (pinfunction "1_1") (pintype "passive"))
      (node (ref "IC47") (pin "1") (pinfunction "VO1_1") (pintype "input"))
      (node (ref "L15") (pin "2") (pinfunction "2_2") (pintype "passive"))
      (node (ref "R241") (pin "2") (pinfunction "2_2") (pintype "passive"))
    )
    (net (code "7") (name "+2V5") (class "Default")
      (node (ref "C259") (pin "1") (pinfunction "1_1") (pintype "passive"))
      (node (ref "C260") (pin "1") (pinfunction "1_1") (pintype "passive"))
      (node (ref "C268") (pin "1") (pinfunction "1_1") (pintype "passive"))
      (node (ref "C269") (pin "2") (pinfunction "2_2") (pintype "passive"))
      (node (ref "C270") (pin "1") (pinfunction "1_1") (pintype "passive"))
      (node (ref "C271") (pin "1") (pinfunction "1_1") (pintype "passive"))
      (node (ref "IC32") (pin "4") (pinfunction "EN_4") (pintype "input"))
      (node (ref "IC34") (pin "4") (pinfunction "EN_4") (pintype "input"))
      (node (ref "IC35") (pin "4") (pinfunction "EN_4") (pintype "input"))
      (node (ref "IC39") (pin "4") (pinfunction "EN_4") (pintype "input"))
      (node (ref "IC46") (pin "7") (pinfunction "EN2_7") (pintype "input"))
      (node (ref "IC47") (pin "24") (pinfunction "EN1_24") (pintype "input"))
      (node (ref "IC47") (pin "6") (pinfunction "VO2_6") (pintype "input"))
      (node (ref "IC48") (pin "4") (pinfunction "EN_4") (pintype "input"))
      (node (ref "L14") (pin "2") (pinfunction "2_2") (pintype "passive"))
      (node (ref "R181") (pin "1") (pinfunction "1_1") (pintype "passive"))
      (node (ref "R190") (pin "1") (pinfunction "1_1") (pintype "passive"))
      (node (ref "R191") (pin "1") (pinfunction "1_1") (pintype "passive"))
      (node (ref "R206") (pin "2") (pinfunction "2_2") (pintype "passive"))
      (node (ref "R207") (pin "1") (pinfunction "1_1") (pintype "passive"))
      (node (ref "R211") (pin "2") (pinfunction "2_2") (pintype "passive"))
      (node (ref "R239") (pin "1") (pinfunction "1_1") (pintype "passive"))
    )
    (net (code "8") (name "+2V5_PLL") (class "Default")
      (node (ref "C263") (pin "2") (pinfunction "2_2") (pintype "passive"))
      (node (ref "C264") (pin "2") (pinfunction "2_2") (pintype "passive"))
      (node (ref "IC34") (pin "8") (pinfunction "OUT_8") (pintype "power_in"))
      (node (ref "R188") (pin "1") (pinfunction "1_1") (pintype "passive"))
    )
    (net (code "9") (name "+3V0_OSC") (class "Default")
      (node (ref "C235") (pin "2") (pinfunction "2_2") (pintype "passive"))
      (node (ref "IC38") (pin "5") (pinfunction "VOUT_5") (pintype "power_in"))
    )
    (net (code "10") (name "+3V0_VM53") (class "Default")
      (node (ref "C236") (pin "2") (pinfunction "2_2") (pintype "passive"))
      (node (ref "IC44") (pin "5") (pinfunction "VOUT_5") (pintype "power_in"))
    )
    (net (code "11") (name "+3V3") (class "Default")
      (node (ref "C250") (pin "2") (pinfunction "2_2") (pintype "passive"))
      (node (ref "C252") (pin "2") (pinfunction "2_2") (pintype "passive"))
      (node (ref "C275") (pin "1") (pinfunction "1_1") (pintype "passive"))
      (node (ref "C283") (pin "2") (pinfunction "2_2") (pintype "passive"))
      (node (ref "C287") (pin "2") (pinfunction "2_2") (pintype "passive"))
      (node (ref "IC34") (pin "1") (pinfunction "IN_1") (pintype "power_in"))
      (node (ref "IC38") (pin "1") (pinfunction "VIN_1") (pintype "power_in"))
      (node (ref "IC38") (pin "3") (pinfunction "~{SHDN}_3") (pintype "input"))
      (node (ref "IC44") (pin "1") (pinfunction "VIN_1") (pintype "power_in"))
      (node (ref "IC48") (pin "8") (pinfunction "OUT_8") (pintype "power_in"))
      (node (ref "R237") (pin "2") (pinfunction "2_2") (pintype "passive"))
    )
    (net (code "12") (name "+3V3_PLL") (class "Default")
      (node (ref "C266") (pin "2") (pinfunction "2_2") (pintype "passive"))
      (node (ref "C267") (pin "2") (pinfunction "2_2") (pintype "passive"))
      (node (ref "IC35") (pin "8") (pinfunction "OUT_8") (pintype "power_in"))
      (node (ref "R189") (pin "1") (pinfunction "1_1") (pintype "passive"))
    )
    (net (code "13") (name "+5VCC_IN") (class "Default")
      (node (ref "C239") (pin "1") (pinfunction "1_1") (pintype "passive"))
      (node (ref "C248") (pin "1") (pinfunction "1_1") (pintype "passive"))
      (node (ref "C249") (pin "1") (pinfunction "1_1") (pintype "passive"))
      (node (ref "C251") (pin "2") (pinfunction "2_2") (pintype "passive"))
      (node (ref "C254") (pin "1") (pinfunction "1_1") (pintype "passive"))
      (node (ref "C255") (pin "2") (pinfunction "2_2") (pintype "passive"))
      (node (ref "C257") (pin "1") (pinfunction "1_1") (pintype "passive"))
      (node (ref "C258") (pin "1") (pinfunction "1_1") (pintype "passive"))
      (node (ref "C274") (pin "2") (pinfunction "2_2") (pintype "passive"))
      (node (ref "C276") (pin "2") (pinfunction "2_2") (pintype "passive"))
      (node (ref "C278") (pin "1") (pinfunction "1_1") (pintype "passive"))
      (node (ref "C279") (pin "1") (pinfunction "1_1") (pintype "passive"))
      (node (ref "C280") (pin "1") (pinfunction "1_1") (pintype "passive"))
      (node (ref "C281") (pin "2") (pinfunction "2_2") (pintype "passive"))
      (node (ref "C303") (pin "2") (pinfunction "2_2") (pintype "passive"))
      (node (ref "C305") (pin "1") (pinfunction "1_1") (pintype "passive"))
      (node (ref "C306") (pin "1") (pinfunction "1_1") (pintype "passive"))
      (node (ref "C307") (pin "1") (pinfunction "1_1") (pintype "passive"))
      (node (ref "C322") (pin "2") (pinfunction "2_2") (pintype "passive"))
      (node (ref "D16") (pin "2") (pinfunction "A_2") (pintype "passive"))
      (node (ref "IC32") (pin "3") (pinfunction "VCC_3") (pintype "power_in"))
      (node (ref "IC34") (pin "3") (pinfunction "VCC_3") (pintype "power_in"))
      (node (ref "IC35") (pin "3") (pinfunction "VCC_3") (pintype "power_in"))
      (node (ref "IC39") (pin "3") (pinfunction "VCC_3") (pintype "power_in"))
      (node (ref "IC46") (pin "17") (pinfunction "VIN_17") (pintype "input"))
      (node (ref "IC46") (pin "24") (pinfunction "EN1_24") (pintype "input"))
      (node (ref "IC47") (pin "17") (pinfunction "VIN_17") (pintype "input"))
      (node (ref "IC48") (pin "3") (pinfunction "VCC_3") (pintype "power_in"))
      (node (ref "R243") (pin "2") (pinfunction "2_2") (pintype "passive"))
      (node (ref "T2") (pin "5") (pinfunction "D_5") (pintype "passive"))
      (node (ref "T2") (pin "6") (pinfunction "D_6") (pintype "passive"))
      (node (ref "T3") (pin "5") (pinfunction "D_5") (pintype "passive"))
      (node (ref "T3") (pin "6") (pinfunction "D_6") (pintype "passive"))
      (node (ref "T4") (pin "5") (pinfunction "D_5") (pintype "passive"))
      (node (ref "T4") (pin "6") (pinfunction "D_6") (pintype "passive"))
      (node (ref "T5") (pin "5") (pinfunction "D_5") (pintype "passive"))
      (node (ref "T5") (pin "6") (pinfunction "D_6") (pintype "passive"))
    )
    (net (code "14") (name "/+1V0_GTX_PG") (class "Default")
      (node (ref "IC39") (pin "2") (pinfunction "PG_2") (pintype "open_collector"))
      (node (ref "R207") (pin "2") (pinfunction "2_2") (pintype "passive"))
    )
    (net (code "15") (name "/+1V2_GTX_PG") (class "Default")
      (node (ref "IC32") (pin "2") (pinfunction "PG_2") (pintype "open_collector"))
      (node (ref "R181") (pin "2") (pinfunction "2_2") (pintype "passive"))
    )
    (net (code "16") (name "/+2V5_PLL_PG") (class "Default")
      (node (ref "IC34") (pin "2") (pinfunction "PG_2") (pintype "open_collector"))
      (node (ref "R190") (pin "2") (pinfunction "2_2") (pintype "passive"))
    )
    (net (code "17") (name "/+3V0_VM53_EN") (class "Default")
      (node (ref "IC44") (pin "3") (pinfunction "~{SHDN}_3") (pintype "input"))
      (node (ref "R211") (pin "1") (pinfunction "1_1") (pintype "passive"))
    )
    (net (code "18") (name "/+3V3_PG") (class "Default")
      (node (ref "IC48") (pin "2") (pinfunction "PG_2") (pintype "open_collector"))
      (node (ref "R239") (pin "2") (pinfunction "2_2") (pintype "passive"))
    )
    (net (code "19") (name "/+3V3_PLL_PG") (class "Default")
      (node (ref "IC35") (pin "2") (pinfunction "PG_2") (pintype "open_collector"))
      (node (ref "R191") (pin "2") (pinfunction "2_2") (pintype "passive"))
    )
    (net (code "20") (name "/LDO_IN") (class "Default")
      (node (ref "C277") (pin "1") (pinfunction "1_1") (pintype "passive"))
      (node (ref "C304") (pin "1") (pinfunction "1_1") (pintype "passive"))
      (node (ref "D16") (pin "1") (pinfunction "C_1") (pintype "passive"))
      (node (ref "IC35") (pin "1") (pinfunction "IN_1") (pintype "power_in"))
      (node (ref "IC48") (pin "1") (pinfunction "IN_1") (pintype "power_in"))
    )
    (net (code "22") (name "GND") (class "Default")
      (node (ref "C235") (pin "1") (pinfunction "1_1") (pintype "passive"))
      (node (ref "C236") (pin "1") (pinfunction "1_1") (pintype "passive"))
      (node (ref "C237") (pin "1") (pinfunction "1_1") (pintype "passive"))
      (node (ref "C238") (pin "2") (pinfunction "2_2") (pintype "passive"))
      (node (ref "C239") (pin "2") (pinfunction "2_2") (pintype "passive"))
      (node (ref "C245") (pin "1") (pinfunction "1_1") (pintype "passive"))
      (node (ref "C246") (pin "1") (pinfunction "1_1") (pintype "passive"))
      (node (ref "C247") (pin "1") (pinfunction "1_1") (pintype "passive"))
      (node (ref "C248") (pin "2") (pinfunction "2_2") (pintype "passive"))
      (node (ref "C249") (pin "2") (pinfunction "2_2") (pintype "passive"))
      (node (ref "C250") (pin "1") (pinfunction "1_1") (pintype "passive"))
      (node (ref "C251") (pin "1") (pinfunction "1_1") (pintype "passive"))
      (node (ref "C252") (pin "1") (pinfunction "1_1") (pintype "passive"))
      (node (ref "C254") (pin "2") (pinfunction "2_2") (pintype "passive"))
      (node (ref "C255") (pin "1") (pinfunction "1_1") (pintype "passive"))
      (node (ref "C256") (pin "2") (pinfunction "2_2") (pintype "passive"))
      (node (ref "C257") (pin "2") (pinfunction "2_2") (pintype "passive"))
      (node (ref "C258") (pin "2") (pinfunction "2_2") (pintype "passive"))
      (node (ref "C259") (pin "2") (pinfunction "2_2") (pintype "passive"))
      (node (ref "C260") (pin "2") (pinfunction "2_2") (pintype "passive"))
      (node (ref "C262") (pin "1") (pinfunction "1_1") (pintype "passive"))
      (node (ref "C263") (pin "1") (pinfunction "1_1") (pintype "passive"))
      (node (ref "C264") (pin "1") (pinfunction "1_1") (pintype "passive"))
      (node (ref "C265") (pin "1") (pinfunction "1_1") (pintype "passive"))
      (node (ref "C266") (pin "1") (pinfunction "1_1") (pintype "passive"))
      (node (ref "C267") (pin "1") (pinfunction "1_1") (pintype "passive"))
      (node (ref "C268") (pin "2") (pinfunction "2_2") (pintype "passive"))
      (node (ref "C269") (pin "1") (pinfunction "1_1") (pintype "passive"))
      (node (ref "C270") (pin "2") (pinfunction "2_2") (pintype "passive"))
      (node (ref "C271") (pin "2") (pinfunction "2_2") (pintype "passive"))
      (node (ref "C272") (pin "1") (pinfunction "1_1") (pintype "passive"))
      (node (ref "C273") (pin "2") (pinfunction "2_2") (pintype "passive"))
      (node (ref "C274") (pin "1") (pinfunction "1_1") (pintype "passive"))
      (node (ref "C275") (pin "2") (pinfunction "2_2") (pintype "passive"))
      (node (ref "C276") (pin "1") (pinfunction "1_1") (pintype "passive"))
      (node (ref "C277") (pin "2") (pinfunction "2_2") (pintype "passive"))
      (node (ref "C278") (pin "2") (pinfunction "2_2") (pintype "passive"))
      (node (ref "C279") (pin "2") (pinfunction "2_2") (pintype "passive"))
      (node (ref "C280") (pin "2") (pinfunction "2_2") (pintype "passive"))
      (node (ref "C281") (pin "1") (pinfunction "1_1") (pintype "passive"))
      (node (ref "C282") (pin "1") (pinfunction "1_1") (pintype "passive"))
      (node (ref "C283") (pin "1") (pinfunction "1_1") (pintype "passive"))
      (node (ref "C287") (pin "1") (pinfunction "1_1") (pintype "passive"))
      (node (ref "C288") (pin "2") (pinfunction "2_2") (pintype "passive"))
      (node (ref "C289") (pin "2") (pinfunction "2_2") (pintype "passive"))
      (node (ref "C290") (pin "2") (pinfunction "2_2") (pintype "passive"))
      (node (ref "C291") (pin "2") (pinfunction "2_2") (pintype "passive"))
      (node (ref "C292") (pin "2") (pinfunction "2_2") (pintype "passive"))
      (node (ref "C294") (pin "2") (pinfunction "2_2") (pintype "passive"))
      (node (ref "C295") (pin "1") (pinfunction "1_1") (pintype "passive"))
      (node (ref "C296") (pin "2") (pinfunction "2_2") (pintype "passive"))
      (node (ref "C297") (pin "1") (pinfunction "1_1") (pintype "passive"))
      (node (ref "C300") (pin "2") (pinfunction "2_2") (pintype "passive"))
      (node (ref "C301") (pin "2") (pinfunction "2_2") (pintype "passive"))
      (node (ref "C302") (pin "2") (pinfunction "2_2") (pintype "passive"))
      (node (ref "C303") (pin "1") (pinfunction "1_1") (pintype "passive"))
      (node (ref "C304") (pin "2") (pinfunction "2_2") (pintype "passive"))
      (node (ref "C305") (pin "2") (pinfunction "2_2") (pintype "passive"))
      (node (ref "C306") (pin "2") (pinfunction "2_2") (pintype "passive"))
      (node (ref "C307") (pin "2") (pinfunction "2_2") (pintype "passive"))
      (node (ref "C310") (pin "1") (pinfunction "1_1") (pintype "passive"))
      (node (ref "C311") (pin "1") (pinfunction "1_1") (pintype "passive"))
      (node (ref "C312") (pin "1") (pinfunction "1_1") (pintype "passive"))
      (node (ref "C322") (pin "1") (pinfunction "1_1") (pintype "passive"))
      (node (ref "C323") (pin "2") (pinfunction "2_2") (pintype "passive"))
      (node (ref "C427") (pin "2") (pinfunction "2_2") (pintype "passive"))
      (node (ref "C428") (pin "2") (pinfunction "2_2") (pintype "passive"))
      (node (ref "C429") (pin "2") (pinfunction "2_2") (pintype "passive"))
      (node (ref "C430") (pin "1") (pinfunction "1_1") (pintype "passive"))
      (node (ref "C431") (pin "2") (pinfunction "2_2") (pintype "passive"))
      (node (ref "C432") (pin "2") (pinfunction "2_2") (pintype "passive"))
      (node (ref "IC32") (pin "5") (pinfunction "GND_5") (pintype "power_in"))
      (node (ref "IC34") (pin "5") (pinfunction "GND_5") (pintype "power_in"))
      (node (ref "IC35") (pin "5") (pinfunction "GND_5") (pintype "power_in"))
      (node (ref "IC38") (pin "2") (pinfunction "VSS_2") (pintype "power_in"))
      (node (ref "IC39") (pin "5") (pinfunction "GND_5") (pintype "power_in"))
      (node (ref "IC44") (pin "2") (pinfunction "VSS_2") (pintype "power_in"))
      (node (ref "IC46") (pin "12") (pinfunction "PGND2_12") (pintype "power_in"))
      (node (ref "IC46") (pin "19") (pinfunction "PGND1_19") (pintype "power_in"))
      (node (ref "IC46") (pin "25") (pinfunction "EP_25") (pintype "power_in"))
      (node (ref "IC46") (pin "3") (pinfunction "GND_3") (pintype "power_in"))
      (node (ref "IC46") (pin "4") (pinfunction "TEST1_4") (pintype "bidirectional"))
      (node (ref "IC47") (pin "12") (pinfunction "PGND2_12") (pintype "power_in"))
      (node (ref "IC47") (pin "19") (pinfunction "PGND1_19") (pintype "power_in"))
      (node (ref "IC47") (pin "25") (pinfunction "EP_25") (pintype "power_in"))
      (node (ref "IC47") (pin "3") (pinfunction "GND_3") (pintype "power_in"))
      (node (ref "IC47") (pin "4") (pinfunction "TEST1_4") (pintype "bidirectional"))
      (node (ref "IC48") (pin "5") (pinfunction "GND_5") (pintype "power_in"))
      (node (ref "R178") (pin "1") (pinfunction "1_1") (pintype "passive"))
      (node (ref "R185") (pin "1") (pinfunction "1_1") (pintype "passive"))
      (node (ref "R186") (pin "1") (pinfunction "1_1") (pintype "passive"))
      (node (ref "R204") (pin "1") (pinfunction "1_1") (pintype "passive"))
      (node (ref "R209") (pin "2") (pinfunction "2_2") (pintype "passive"))
      (node (ref "R227") (pin "1") (pinfunction "1_1") (pintype "passive"))
      (node (ref "R229") (pin "2") (pinfunction "2_2") (pintype "passive"))
      (node (ref "R231") (pin "2") (pinfunction "2_2") (pintype "passive"))
      (node (ref "R232") (pin "2") (pinfunction "2_2") (pintype "passive"))
      (node (ref "R234") (pin "2") (pinfunction "2_2") (pintype "passive"))
      (node (ref "R235") (pin "1") (pinfunction "1_1") (pintype "passive"))
      (node (ref "R236") (pin "1") (pinfunction "1_1") (pintype "passive"))
      (node (ref "R238") (pin "2") (pinfunction "2_2") (pintype "passive"))
      (node (ref "R240") (pin "2") (pinfunction "2_2") (pintype "passive"))
      (node (ref "R242") (pin "2") (pinfunction "2_2") (pintype "passive"))
      (node (ref "T2") (pin "1") (pinfunction "S_1") (pintype "passive"))
      (node (ref "T3") (pin "1") (pinfunction "S_1") (pintype "passive"))
      (node (ref "T4") (pin "1") (pinfunction "S_1") (pintype "passive"))
      (node (ref "T5") (pin "1") (pinfunction "S_1") (pintype "passive"))
    )
    (net (code "23") (name "Net-(D3-A)") (class "Default")
      (node (ref "D3") (pin "1") (pinfunction "A_1") (pintype "passive"))
      (node (ref "IC47") (pin "7") (pinfunction "EN2_7") (pintype "input"))
      (node (ref "R243") (pin "1") (pinfunction "1_1") (pintype "passive"))
    )
    (net (code "24") (name "Net-(D3-K)") (class "Default")
      (node (ref "D3") (pin "2") (pinfunction "K_2") (pintype "passive"))
      (node (ref "D4") (pin "1") (pinfunction "A_1") (pintype "passive"))
    )
    (net (code "25") (name "Net-(IC32-FB)") (class "Default")
      (node (ref "IC32") (pin "7") (pinfunction "FB_7") (pintype "passive"))
      (node (ref "R178") (pin "2") (pinfunction "2_2") (pintype "passive"))
      (node (ref "R180") (pin "1") (pinfunction "1_1") (pintype "passive"))
    )
    (net (code "26") (name "Net-(IC32-SS)") (class "Default")
      (node (ref "C245") (pin "2") (pinfunction "2_2") (pintype "passive"))
      (node (ref "IC32") (pin "6") (pinfunction "SS_6") (pintype "passive"))
    )
    (net (code "27") (name "Net-(IC34-FB)") (class "Default")
      (node (ref "IC34") (pin "7") (pinfunction "FB_7") (pintype "passive"))
      (node (ref "R185") (pin "2") (pinfunction "2_2") (pintype "passive"))
      (node (ref "R188") (pin "2") (pinfunction "2_2") (pintype "passive"))
    )
    (net (code "28") (name "Net-(IC34-SS)") (class "Default")
      (node (ref "C262") (pin "2") (pinfunction "2_2") (pintype "passive"))
      (node (ref "IC34") (pin "6") (pinfunction "SS_6") (pintype "passive"))
    )
    (net (code "29") (name "Net-(IC35-FB)") (class "Default")
      (node (ref "IC35") (pin "7") (pinfunction "FB_7") (pintype "passive"))
      (node (ref "R186") (pin "2") (pinfunction "2_2") (pintype "passive"))
      (node (ref "R189") (pin "2") (pinfunction "2_2") (pintype "passive"))
    )
    (net (code "30") (name "Net-(IC35-SS)") (class "Default")
      (node (ref "C265") (pin "2") (pinfunction "2_2") (pintype "passive"))
      (node (ref "IC35") (pin "6") (pinfunction "SS_6") (pintype "passive"))
    )
    (net (code "31") (name "Net-(IC39-FB)") (class "Default")
      (node (ref "IC39") (pin "7") (pinfunction "FB_7") (pintype "passive"))
      (node (ref "R204") (pin "2") (pinfunction "2_2") (pintype "passive"))
      (node (ref "R205") (pin "1") (pinfunction "1_1") (pintype "passive"))
    )
    (net (code "32") (name "Net-(IC39-SS)") (class "Default")
      (node (ref "C310") (pin "2") (pinfunction "2_2") (pintype "passive"))
      (node (ref "IC39") (pin "6") (pinfunction "SS_6") (pintype "passive"))
    )
    (net (code "33") (name "Net-(IC46-DRVH1)") (class "Default")
      (node (ref "IC46") (pin "22") (pinfunction "DRVH1_22") (pintype "output"))
      (node (ref "T3") (pin "4") (pinfunction "G_4") (pintype "passive"))
    )
    (net (code "34") (name "Net-(IC46-DRVH2)") (class "Default")
      (node (ref "IC46") (pin "9") (pinfunction "DRVH2_9") (pintype "output"))
      (node (ref "T2") (pin "4") (pinfunction "G_4") (pintype "passive"))
    )
    (net (code "35") (name "Net-(IC46-DRVL1)") (class "Default")
      (node (ref "IC46") (pin "20") (pinfunction "DRVL1_20") (pintype "output"))
      (node (ref "T3") (pin "2") (pinfunction "G_2") (pintype "passive"))
    )
    (net (code "36") (name "Net-(IC46-DRVL2)") (class "Default")
      (node (ref "IC46") (pin "11") (pinfunction "DRVL2_11") (pintype "output"))
      (node (ref "T2") (pin "2") (pinfunction "G_2") (pintype "passive"))
    )
    (net (code "37") (name "Net-(IC46-SW1)") (class "Default")
      (node (ref "C253") (pin "2") (pinfunction "2_2") (pintype "passive"))
      (node (ref "IC46") (pin "21") (pinfunction "SW1_21") (pintype "bidirectional"))
      (node (ref "L13") (pin "1") (pinfunction "1_1") (pintype "passive"))
      (node (ref "T3") (pin "3") (pinfunction "S_3") (pintype "passive"))
      (node (ref "T3") (pin "7") (pinfunction "D_7") (pintype "passive"))
      (node (ref "T3") (pin "8") (pinfunction "D_8") (pintype "passive"))
    )
    (net (code "38") (name "Net-(IC46-SW2)") (class "Default")
      (node (ref "C207") (pin "2") (pinfunction "2_2") (pintype "passive"))
      (node (ref "IC46") (pin "10") (pinfunction "SW2_10") (pintype "bidirectional"))
      (node (ref "L11") (pin "1") (pinfunction "1_1") (pintype "passive"))
      (node (ref "T2") (pin "3") (pinfunction "S_3") (pintype "passive"))
      (node (ref "T2") (pin "7") (pinfunction "D_7") (pintype "passive"))
      (node (ref "T2") (pin "8") (pinfunction "D_8") (pintype "passive"))
    )
    (net (code "39") (name "Net-(IC46-TEST2)") (class "Default")
      (node (ref "IC46") (pin "14") (pinfunction "TEST2_14") (pintype "input"))
      (node (ref "R210") (pin "2") (pinfunction "2_2") (pintype "passive"))
      (node (ref "R227") (pin "2") (pinfunction "2_2") (pintype "passive"))
    )
    (net (code "40") (name "Net-(IC46-TRIP1)") (class "Default")
      (node (ref "IC46") (pin "18") (pinfunction "TRIP1_18") (pintype "input"))
      (node (ref "R229") (pin "1") (pinfunction "1_1") (pintype "passive"))
    )
    (net (code "41") (name "Net-(IC46-TRIP2)") (class "Default")
      (node (ref "IC46") (pin "13") (pinfunction "TRIP2_13") (pintype "input"))
      (node (ref "R209") (pin "1") (pinfunction "1_1") (pintype "passive"))
    )
    (net (code "42") (name "Net-(IC46-V5FILT)") (class "Default")
      (node (ref "C237") (pin "2") (pinfunction "2_2") (pintype "passive"))
      (node (ref "IC46") (pin "15") (pinfunction "V5FILT_15") (pintype "input"))
      (node (ref "R210") (pin "1") (pinfunction "1_1") (pintype "passive"))
    )
    (net (code "43") (name "Net-(IC46-VBST1)") (class "Default")
      (node (ref "C253") (pin "1") (pinfunction "1_1") (pintype "passive"))
      (node (ref "IC46") (pin "23") (pinfunction "VBST1_23") (pintype "input"))
    )
    (net (code "44") (name "Net-(IC46-VBST2)") (class "Default")
      (node (ref "C207") (pin "1") (pinfunction "1_1") (pintype "passive"))
      (node (ref "IC46") (pin "8") (pinfunction "VBST2_8") (pintype "input"))
    )
    (net (code "45") (name "Net-(IC46-VFB1)") (class "Default")
      (node (ref "IC46") (pin "2") (pinfunction "VFB1_2") (pintype "input"))
      (node (ref "R230") (pin "1") (pinfunction "1_1") (pintype "passive"))
      (node (ref "R231") (pin "1") (pinfunction "1_1") (pintype "passive"))
    )
    (net (code "46") (name "Net-(IC46-VFB2)") (class "Default")
      (node (ref "IC46") (pin "5") (pinfunction "VFB2_5") (pintype "input"))
      (node (ref "R228") (pin "2") (pinfunction "2_2") (pintype "passive"))
      (node (ref "R238") (pin "1") (pinfunction "1_1") (pintype "passive"))
    )
    (net (code "47") (name "Net-(IC46-VREG5)") (class "Default")
      (node (ref "C238") (pin "1") (pinfunction "1_1") (pintype "passive"))
      (node (ref "IC46") (pin "16") (pinfunction "VREG5_16") (pintype "output"))
    )
    (net (code "48") (name "Net-(IC47-DRVH1)") (class "Default")
      (node (ref "IC47") (pin "22") (pinfunction "DRVH1_22") (pintype "output"))
      (node (ref "T5") (pin "4") (pinfunction "G_4") (pintype "passive"))
    )
    (net (code "49") (name "Net-(IC47-DRVH2)") (class "Default")
      (node (ref "IC47") (pin "9") (pinfunction "DRVH2_9") (pintype "output"))
      (node (ref "T4") (pin "4") (pinfunction "G_4") (pintype "passive"))
    )
    (net (code "50") (name "Net-(IC47-DRVL1)") (class "Default")
      (node (ref "IC47") (pin "20") (pinfunction "DRVL1_20") (pintype "output"))
      (node (ref "T5") (pin "2") (pinfunction "G_2") (pintype "passive"))
    )
    (net (code "51") (name "Net-(IC47-DRVL2)") (class "Default")
      (node (ref "IC47") (pin "11") (pinfunction "DRVL2_11") (pintype "output"))
      (node (ref "T4") (pin "2") (pinfunction "G_2") (pintype "passive"))
    )
    (net (code "52") (name "Net-(IC47-SW1)") (class "Default")
      (node (ref "C293") (pin "2") (pinfunction "2_2") (pintype "passive"))
      (node (ref "IC47") (pin "21") (pinfunction "SW1_21") (pintype "bidirectional"))
      (node (ref "L15") (pin "1") (pinfunction "1_1") (pintype "passive"))
      (node (ref "T5") (pin "3") (pinfunction "S_3") (pintype "passive"))
      (node (ref "T5") (pin "7") (pinfunction "D_7") (pintype "passive"))
      (node (ref "T5") (pin "8") (pinfunction "D_8") (pintype "passive"))
    )
    (net (code "53") (name "Net-(IC47-SW2)") (class "Default")
      (node (ref "C261") (pin "2") (pinfunction "2_2") (pintype "passive"))
      (node (ref "IC47") (pin "10") (pinfunction "SW2_10") (pintype "bidirectional"))
      (node (ref "L14") (pin "1") (pinfunction "1_1") (pintype "passive"))
      (node (ref "T4") (pin "3") (pinfunction "S_3") (pintype "passive"))
      (node (ref "T4") (pin "7") (pinfunction "D_7") (pintype "passive"))
      (node (ref "T4") (pin "8") (pinfunction "D_8") (pintype "passive"))
    )
    (net (code "54") (name "Net-(IC47-TEST2)") (class "Default")
      (node (ref "IC47") (pin "14") (pinfunction "TEST2_14") (pintype "input"))
      (node (ref "R233") (pin "2") (pinfunction "2_2") (pintype "passive"))
      (node (ref "R235") (pin "2") (pinfunction "2_2") (pintype "passive"))
    )
    (net (code "55") (name "Net-(IC47-TRIP1)") (class "Default")
      (node (ref "IC47") (pin "18") (pinfunction "TRIP1_18") (pintype "input"))
      (node (ref "R240") (pin "1") (pinfunction "1_1") (pintype "passive"))
    )
    (net (code "56") (name "Net-(IC47-TRIP2)") (class "Default")
      (node (ref "IC47") (pin "13") (pinfunction "TRIP2_13") (pintype "input"))
      (node (ref "R232") (pin "1") (pinfunction "1_1") (pintype "passive"))
    )
    (net (code "57") (name "Net-(IC47-V5FILT)") (class "Default")
      (node (ref "C272") (pin "2") (pinfunction "2_2") (pintype "passive"))
      (node (ref "IC47") (pin "15") (pinfunction "V5FILT_15") (pintype "input"))
      (node (ref "R233") (pin "1") (pinfunction "1_1") (pintype "passive"))
    )
    (net (code "58") (name "Net-(IC47-VBST1)") (class "Default")
      (node (ref "C293") (pin "1") (pinfunction "1_1") (pintype "passive"))
      (node (ref "IC47") (pin "23") (pinfunction "VBST1_23") (pintype "input"))
    )
    (net (code "59") (name "Net-(IC47-VBST2)") (class "Default")
      (node (ref "C261") (pin "1") (pinfunction "1_1") (pintype "passive"))
      (node (ref "IC47") (pin "8") (pinfunction "VBST2_8") (pintype "input"))
    )
    (net (code "60") (name "Net-(IC47-VFB1)") (class "Default")
      (node (ref "IC47") (pin "2") (pinfunction "VFB1_2") (pintype "input"))
      (node (ref "R241") (pin "1") (pinfunction "1_1") (pintype "passive"))
      (node (ref "R242") (pin "1") (pinfunction "1_1") (pintype "passive"))
    )
    (net (code "61") (name "Net-(IC47-VFB2)") (class "Default")
      (node (ref "IC47") (pin "5") (pinfunction "VFB2_5") (pintype "input"))
      (node (ref "R206") (pin "1") (pinfunction "1_1") (pintype "passive"))
      (node (ref "R234") (pin "1") (pinfunction "1_1") (pintype "passive"))
    )
    (net (code "62") (name "Net-(IC47-VREG5)") (class "Default")
      (node (ref "C273") (pin "1") (pinfunction "1_1") (pintype "passive"))
      (node (ref "IC47") (pin "16") (pinfunction "VREG5_16") (pintype "output"))
    )
    (net (code "63") (name "Net-(IC48-FB)") (class "Default")
      (node (ref "IC48") (pin "7") (pinfunction "FB_7") (pintype "passive"))
      (node (ref "R236") (pin "2") (pinfunction "2_2") (pintype "passive"))
      (node (ref "R237") (pin "1") (pinfunction "1_1") (pintype "passive"))
    )
    (net (code "64") (name "Net-(IC48-SS)") (class "Default")
      (node (ref "C282") (pin "2") (pinfunction "2_2") (pintype "passive"))
      (node (ref "IC48") (pin "6") (pinfunction "SS_6") (pintype "passive"))
    )
    (net (code "65") (name "unconnected-(IC38-NC-Pad4)") (class "Default")
      (node (ref "IC38") (pin "4") (pinfunction "NC_4") (pintype "passive+no_connect"))
    )
    (net (code "66") (name "unconnected-(IC44-NC-Pad4)") (class "Default")
      (node (ref "IC44") (pin "4") (pinfunction "NC_4") (pintype "passive+no_connect"))
    )
  )
)
